# 32U4-Programmer.net
KiCad netlist of a schematic drawn in EAGLE
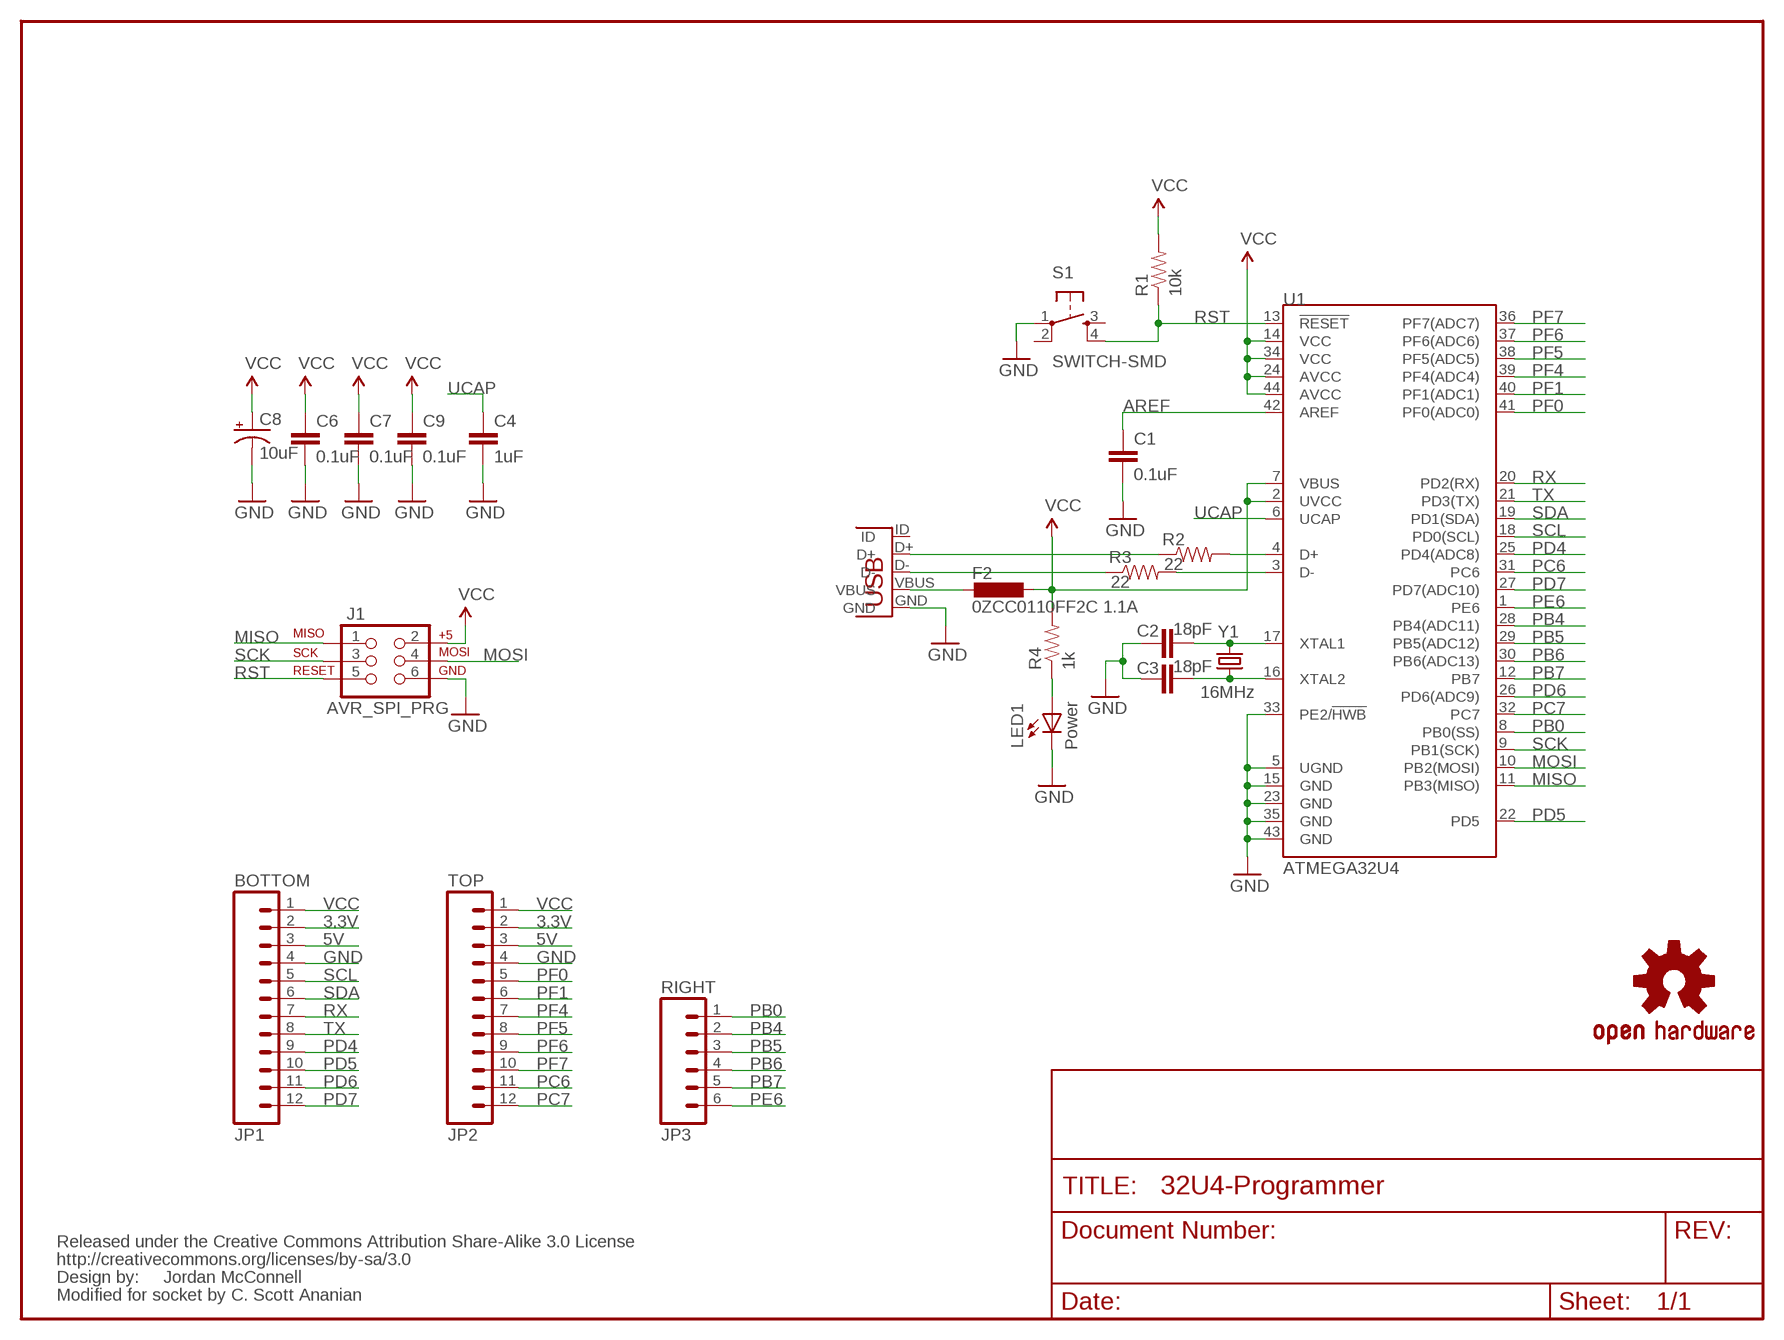
[diagram p0: schematic, sheet 1]

(export (version "E")
  (design (tool "Eeschema 10.0.6"))
  (components
    (comp (ref "C1")
      (value "0.1uF")
      (footprint "eagle-import:CAP-PTH-SMALL")
      (libsource (lib "eagle-import") (part "CAPPTH"))
    )
    (comp (ref "C2")
      (value "18pF")
      (footprint "eagle-import:CAP-PTH-SMALL")
      (libsource (lib "eagle-import") (part "CAPPTH"))
    )
    (comp (ref "C3")
      (value "18pF")
      (footprint "eagle-import:CAP-PTH-SMALL")
      (libsource (lib "eagle-import") (part "CAPPTH"))
    )
    (comp (ref "C4")
      (value "1uF")
      (footprint "eagle-import:CAP-PTH-SMALL")
      (libsource (lib "eagle-import") (part "CAPPTH"))
    )
    (comp (ref "C6")
      (value "0.1uF")
      (footprint "eagle-import:CAP-PTH-SMALL")
      (libsource (lib "eagle-import") (part "CAPPTH"))
    )
    (comp (ref "C7")
      (value "0.1uF")
      (footprint "eagle-import:CAP-PTH-SMALL")
      (libsource (lib "eagle-import") (part "CAPPTH"))
    )
    (comp (ref "C8")
      (value "10uF")
      (footprint "eagle-import:CPOL-RADIAL-10UF-25V")
      (libsource (lib "eagle-import") (part "CAP_POLPTH2"))
    )
    (comp (ref "C9")
      (value "0.1uF")
      (footprint "eagle-import:CAP-PTH-SMALL")
      (libsource (lib "eagle-import") (part "CAPPTH"))
    )
    (comp (ref "F2")
      (value "0ZCC0110FF2C 1.1A")
      (footprint "eagle-import:L1812")
      (libsource (lib "eagle-import") (part "L-EUL1812"))
    )
    (comp (ref "J1")
      (value "AVR_SPI_PRG")
      (footprint "eagle-import:2X3")
      (libsource (lib "eagle-import") (part "AVR_SPI_PRG_6PTH"))
    )
    (comp (ref "JP1")
      (value "BOTTOM")
      (footprint "eagle-import:1X12")
      (libsource (lib "eagle-import") (part "M12PTH"))
    )
    (comp (ref "JP2")
      (value "TOP")
      (footprint "eagle-import:1X12")
      (libsource (lib "eagle-import") (part "M12PTH"))
    )
    (comp (ref "JP3")
      (value "RIGHT")
      (footprint "eagle-import:1X06")
      (libsource (lib "eagle-import") (part "M06SIP"))
    )
    (comp (ref "LED1")
      (value "Power")
      (footprint "eagle-import:LED3MM-KIT")
      (libsource (lib "eagle-import") (part "LED3MM-KIT"))
    )
    (comp (ref "R1")
      (value "10k")
      (footprint "eagle-import:AXIAL-0.3")
      (libsource (lib "eagle-import") (part "RESISTORAXIAL-0.3"))
    )
    (comp (ref "R2")
      (value "22")
      (footprint "eagle-import:AXIAL-0.3")
      (libsource (lib "eagle-import") (part "RESISTORAXIAL-0.3"))
    )
    (comp (ref "R3")
      (value "22")
      (footprint "eagle-import:AXIAL-0.3")
      (libsource (lib "eagle-import") (part "RESISTORAXIAL-0.3"))
    )
    (comp (ref "R4")
      (value "1k")
      (footprint "eagle-import:AXIAL-0.3")
      (libsource (lib "eagle-import") (part "RESISTORAXIAL-0.3"))
    )
    (comp (ref "S1")
      (value "SWITCH-SMD")
      (footprint "eagle-import:TACTILE-PTH")
      (libsource (lib "eagle-import") (part "TAC_SWITCHPTH"))
    )
    (comp (ref "U$6")
      (value "OSHW-LOGOM")
      (footprint "eagle-import:OSHW-LOGO-M")
      (libsource (lib "eagle-import") (part "OSHW-LOGOM"))
    )
    (comp (ref "U$7")
      (value "CREATIVE_COMMONS")
      (footprint "eagle-import:CREATIVE_COMMONS")
      (libsource (lib "eagle-import") (part "CREATIVE_COMMONS"))
    )
    (comp (ref "U1")
      (value "ATMEGA32U4")
      (footprint "eagle-import:TQFP44-SOCKET")
      (libsource (lib "eagle-import") (part "ATMEGA32U4TQFP44-SOCKET"))
    )
    (comp (ref "X1")
      (value "USBMINIB")
      (footprint "eagle-import:USB-MB-H2")
      (libsource (lib "eagle-import") (part "USBMINIB"))
    )
    (comp (ref "Y1")
      (value "16MHz")
      (footprint "eagle-import:HC49US")
      (libsource (lib "eagle-import") (part "CRYSTALHC49US"))
    )
  )
  (nets
    (net (code "1") (name "/3.3V") (class "Default")
      (node (ref "JP1") (pin "2") (pinfunction "2_2") (pintype "passive"))
      (node (ref "JP2") (pin "2") (pinfunction "2_2") (pintype "passive"))
    )
    (net (code "2") (name "/5V") (class "Default")
      (node (ref "JP1") (pin "3") (pinfunction "3_3") (pintype "passive"))
      (node (ref "JP2") (pin "3") (pinfunction "3_3") (pintype "passive"))
    )
    (net (code "3") (name "/AREF") (class "Default")
      (node (ref "C1") (pin "1") (pinfunction "1_1") (pintype "passive"))
      (node (ref "U1") (pin "42") (pinfunction "AREF_42") (pintype "bidirectional"))
    )
    (net (code "4") (name "/MISO") (class "Default")
      (node (ref "J1") (pin "1") (pinfunction "1_1") (pintype "passive"))
      (node (ref "U1") (pin "11") (pinfunction "PB3(MISO)_11") (pintype "bidirectional"))
    )
    (net (code "5") (name "/MOSI") (class "Default")
      (node (ref "J1") (pin "4") (pinfunction "4_4") (pintype "passive"))
      (node (ref "U1") (pin "10") (pinfunction "PB2(MOSI)_10") (pintype "bidirectional"))
    )
    (net (code "6") (name "/PB0") (class "Default")
      (node (ref "JP3") (pin "1") (pinfunction "1_1") (pintype "passive"))
      (node (ref "U1") (pin "8") (pinfunction "PB0(SS)_8") (pintype "bidirectional"))
    )
    (net (code "7") (name "/PB4") (class "Default")
      (node (ref "JP3") (pin "2") (pinfunction "2_2") (pintype "passive"))
      (node (ref "U1") (pin "28") (pinfunction "PB4(ADC11)_28") (pintype "bidirectional"))
    )
    (net (code "8") (name "/PB5") (class "Default")
      (node (ref "JP3") (pin "3") (pinfunction "3_3") (pintype "passive"))
      (node (ref "U1") (pin "29") (pinfunction "PB5(ADC12)_29") (pintype "bidirectional"))
    )
    (net (code "9") (name "/PB6") (class "Default")
      (node (ref "JP3") (pin "4") (pinfunction "4_4") (pintype "passive"))
      (node (ref "U1") (pin "30") (pinfunction "PB6(ADC13)_30") (pintype "bidirectional"))
    )
    (net (code "10") (name "/PB7") (class "Default")
      (node (ref "JP3") (pin "5") (pinfunction "5_5") (pintype "passive"))
      (node (ref "U1") (pin "12") (pinfunction "PB7_12") (pintype "bidirectional"))
    )
    (net (code "11") (name "/PC6") (class "Default")
      (node (ref "JP2") (pin "11") (pinfunction "11_11") (pintype "passive"))
      (node (ref "U1") (pin "31") (pinfunction "PC6_31") (pintype "bidirectional"))
    )
    (net (code "12") (name "/PC7") (class "Default")
      (node (ref "JP2") (pin "12") (pinfunction "12_12") (pintype "passive"))
      (node (ref "U1") (pin "32") (pinfunction "PC7_32") (pintype "bidirectional"))
    )
    (net (code "13") (name "/PD4") (class "Default")
      (node (ref "JP1") (pin "9") (pinfunction "9_9") (pintype "passive"))
      (node (ref "U1") (pin "25") (pinfunction "PD4(ADC8)_25") (pintype "bidirectional"))
    )
    (net (code "14") (name "/PD5") (class "Default")
      (node (ref "JP1") (pin "10") (pinfunction "10_10") (pintype "passive"))
      (node (ref "U1") (pin "22") (pinfunction "PD5_22") (pintype "bidirectional"))
    )
    (net (code "15") (name "/PD6") (class "Default")
      (node (ref "JP1") (pin "11") (pinfunction "11_11") (pintype "passive"))
      (node (ref "U1") (pin "26") (pinfunction "PD6(ADC9)_26") (pintype "bidirectional"))
    )
    (net (code "16") (name "/PD7") (class "Default")
      (node (ref "JP1") (pin "12") (pinfunction "12_12") (pintype "passive"))
      (node (ref "U1") (pin "27") (pinfunction "PD7(ADC10)_27") (pintype "bidirectional"))
    )
    (net (code "17") (name "/PE6") (class "Default")
      (node (ref "JP3") (pin "6") (pinfunction "6_6") (pintype "passive"))
      (node (ref "U1") (pin "1") (pinfunction "PE6_1") (pintype "bidirectional"))
    )
    (net (code "18") (name "/PF0") (class "Default")
      (node (ref "JP2") (pin "5") (pinfunction "5_5") (pintype "passive"))
      (node (ref "U1") (pin "41") (pinfunction "PF0(ADC0)_41") (pintype "bidirectional"))
    )
    (net (code "19") (name "/PF1") (class "Default")
      (node (ref "JP2") (pin "6") (pinfunction "6_6") (pintype "passive"))
      (node (ref "U1") (pin "40") (pinfunction "PF1(ADC1)_40") (pintype "bidirectional"))
    )
    (net (code "20") (name "/PF4") (class "Default")
      (node (ref "JP2") (pin "7") (pinfunction "7_7") (pintype "passive"))
      (node (ref "U1") (pin "39") (pinfunction "PF4(ADC4)_39") (pintype "bidirectional"))
    )
    (net (code "21") (name "/PF5") (class "Default")
      (node (ref "JP2") (pin "8") (pinfunction "8_8") (pintype "passive"))
      (node (ref "U1") (pin "38") (pinfunction "PF5(ADC5)_38") (pintype "bidirectional"))
    )
    (net (code "22") (name "/PF6") (class "Default")
      (node (ref "JP2") (pin "9") (pinfunction "9_9") (pintype "passive"))
      (node (ref "U1") (pin "37") (pinfunction "PF6(ADC6)_37") (pintype "bidirectional"))
    )
    (net (code "23") (name "/PF7") (class "Default")
      (node (ref "JP2") (pin "10") (pinfunction "10_10") (pintype "passive"))
      (node (ref "U1") (pin "36") (pinfunction "PF7(ADC7)_36") (pintype "bidirectional"))
    )
    (net (code "24") (name "/RST") (class "Default")
      (node (ref "J1") (pin "5") (pinfunction "5_5") (pintype "passive"))
      (node (ref "R1") (pin "P$1") (pinfunction "1_P$1") (pintype "passive"))
      (node (ref "S1") (pin "4") (pinfunction "4_4") (pintype "passive"))
      (node (ref "U1") (pin "13") (pinfunction "~{RESET}_13") (pintype "bidirectional"))
    )
    (net (code "25") (name "/RX") (class "Default")
      (node (ref "JP1") (pin "7") (pinfunction "7_7") (pintype "passive"))
      (node (ref "U1") (pin "20") (pinfunction "PD2(RX)_20") (pintype "bidirectional"))
    )
    (net (code "26") (name "/SCK") (class "Default")
      (node (ref "J1") (pin "3") (pinfunction "3_3") (pintype "passive"))
      (node (ref "U1") (pin "9") (pinfunction "PB1(SCK)_9") (pintype "bidirectional"))
    )
    (net (code "27") (name "/SCL") (class "Default")
      (node (ref "JP1") (pin "5") (pinfunction "5_5") (pintype "passive"))
      (node (ref "U1") (pin "18") (pinfunction "PD0(SCL)_18") (pintype "bidirectional"))
    )
    (net (code "28") (name "/SDA") (class "Default")
      (node (ref "JP1") (pin "6") (pinfunction "6_6") (pintype "passive"))
      (node (ref "U1") (pin "19") (pinfunction "PD1(SDA)_19") (pintype "bidirectional"))
    )
    (net (code "29") (name "/TX") (class "Default")
      (node (ref "JP1") (pin "8") (pinfunction "8_8") (pintype "passive"))
      (node (ref "U1") (pin "21") (pinfunction "PD3(TX)_21") (pintype "bidirectional"))
    )
    (net (code "30") (name "/UCAP") (class "Default")
      (node (ref "C4") (pin "1") (pinfunction "1_1") (pintype "passive"))
      (node (ref "U1") (pin "6") (pinfunction "UCAP_6") (pintype "bidirectional"))
    )
    (net (code "31") (name "GND") (class "Default")
      (node (ref "C1") (pin "2") (pinfunction "2_2") (pintype "passive"))
      (node (ref "C2") (pin "1") (pinfunction "1_1") (pintype "passive"))
      (node (ref "C3") (pin "1") (pinfunction "1_1") (pintype "passive"))
      (node (ref "C4") (pin "2") (pinfunction "2_2") (pintype "passive"))
      (node (ref "C6") (pin "2") (pinfunction "2_2") (pintype "passive"))
      (node (ref "C7") (pin "2") (pinfunction "2_2") (pintype "passive"))
      (node (ref "C8") (pin "2") (pinfunction "-_2") (pintype "passive"))
      (node (ref "C9") (pin "2") (pinfunction "2_2") (pintype "passive"))
      (node (ref "J1") (pin "6") (pinfunction "6_6") (pintype "passive"))
      (node (ref "JP1") (pin "4") (pinfunction "4_4") (pintype "passive"))
      (node (ref "JP2") (pin "4") (pinfunction "4_4") (pintype "passive"))
      (node (ref "LED1") (pin "K") (pinfunction "C_K") (pintype "passive"))
      (node (ref "S1") (pin "1") (pinfunction "1_1") (pintype "passive"))
      (node (ref "U1") (pin "15") (pinfunction "GND_15") (pintype "bidirectional"))
      (node (ref "U1") (pin "23") (pinfunction "GND_23") (pintype "bidirectional"))
      (node (ref "U1") (pin "33") (pinfunction "PE2/~{HWB}_33") (pintype "bidirectional"))
      (node (ref "U1") (pin "35") (pinfunction "GND_35") (pintype "bidirectional"))
      (node (ref "U1") (pin "43") (pinfunction "GND_43") (pintype "bidirectional"))
      (node (ref "U1") (pin "5") (pinfunction "UGND_5") (pintype "bidirectional"))
      (node (ref "X1") (pin "GND") (pinfunction "GND_GND") (pintype "bidirectional"))
    )
    (net (code "32") (name "Net-(F2-Pad2)") (class "Default")
      (node (ref "F2") (pin "2") (pinfunction "2_2") (pintype "passive"))
      (node (ref "X1") (pin "VBUS") (pinfunction "VBUS_VBUS") (pintype "bidirectional"))
    )
    (net (code "33") (name "Net-(R2-1)") (class "Default")
      (node (ref "R2") (pin "P$1") (pinfunction "1_P$1") (pintype "passive"))
      (node (ref "X1") (pin "D+") (pinfunction "D+_D+") (pintype "bidirectional"))
    )
    (net (code "34") (name "Net-(R2-2)") (class "Default")
      (node (ref "R2") (pin "P$2") (pinfunction "2_P$2") (pintype "passive"))
      (node (ref "U1") (pin "4") (pinfunction "D+_4") (pintype "bidirectional"))
    )
    (net (code "35") (name "Net-(R3-1)") (class "Default")
      (node (ref "R3") (pin "P$1") (pinfunction "1_P$1") (pintype "passive"))
      (node (ref "X1") (pin "D-") (pinfunction "D-_D-") (pintype "bidirectional"))
    )
    (net (code "36") (name "Net-(R3-2)") (class "Default")
      (node (ref "R3") (pin "P$2") (pinfunction "2_P$2") (pintype "passive"))
      (node (ref "U1") (pin "3") (pinfunction "D-_3") (pintype "bidirectional"))
    )
    (net (code "37") (name "Net-(R4-1)") (class "Default")
      (node (ref "LED1") (pin "A") (pinfunction "A_A") (pintype "passive"))
      (node (ref "R4") (pin "P$1") (pinfunction "1_P$1") (pintype "passive"))
    )
    (net (code "38") (name "Net-(U1-XTAL1)") (class "Default")
      (node (ref "C2") (pin "2") (pinfunction "2_2") (pintype "passive"))
      (node (ref "U1") (pin "17") (pinfunction "XTAL1_17") (pintype "bidirectional"))
      (node (ref "Y1") (pin "2") (pinfunction "2_2") (pintype "passive"))
    )
    (net (code "39") (name "Net-(U1-XTAL2)") (class "Default")
      (node (ref "C3") (pin "2") (pinfunction "2_2") (pintype "passive"))
      (node (ref "U1") (pin "16") (pinfunction "XTAL2_16") (pintype "bidirectional"))
      (node (ref "Y1") (pin "1") (pinfunction "1_1") (pintype "passive"))
    )
    (net (code "40") (name "VCC") (class "Default")
      (node (ref "C6") (pin "1") (pinfunction "1_1") (pintype "passive"))
      (node (ref "C7") (pin "1") (pinfunction "1_1") (pintype "passive"))
      (node (ref "C8") (pin "1") (pinfunction "+_1") (pintype "passive"))
      (node (ref "C9") (pin "1") (pinfunction "1_1") (pintype "passive"))
      (node (ref "F2") (pin "1") (pinfunction "1_1") (pintype "passive"))
      (node (ref "J1") (pin "2") (pinfunction "2_2") (pintype "passive"))
      (node (ref "JP1") (pin "1") (pinfunction "1_1") (pintype "passive"))
      (node (ref "JP2") (pin "1") (pinfunction "1_1") (pintype "passive"))
      (node (ref "R1") (pin "P$2") (pinfunction "2_P$2") (pintype "passive"))
      (node (ref "R4") (pin "P$2") (pinfunction "2_P$2") (pintype "passive"))
      (node (ref "U1") (pin "14") (pinfunction "VCC_14") (pintype "bidirectional"))
      (node (ref "U1") (pin "2") (pinfunction "UVCC_2") (pintype "bidirectional"))
      (node (ref "U1") (pin "24") (pinfunction "AVCC_24") (pintype "bidirectional"))
      (node (ref "U1") (pin "34") (pinfunction "VCC_34") (pintype "bidirectional"))
      (node (ref "U1") (pin "44") (pinfunction "AVCC_44") (pintype "bidirectional"))
      (node (ref "U1") (pin "7") (pinfunction "VBUS_7") (pintype "bidirectional"))
    )
    (net (code "41") (name "unconnected-(S1-Pad2)") (class "Default")
      (node (ref "S1") (pin "2") (pinfunction "2_2") (pintype "passive"))
    )
    (net (code "42") (name "unconnected-(S1-Pad3)") (class "Default")
      (node (ref "S1") (pin "3") (pinfunction "3_3") (pintype "passive"))
    )
    (net (code "43") (name "unconnected-(X1-PadID)") (class "Default")
      (node (ref "X1") (pin "ID") (pinfunction "ID_ID") (pintype "bidirectional"))
    )
  )
)
